# Vss.net
KiCad netlist of a schematic drawn in Altium Designer
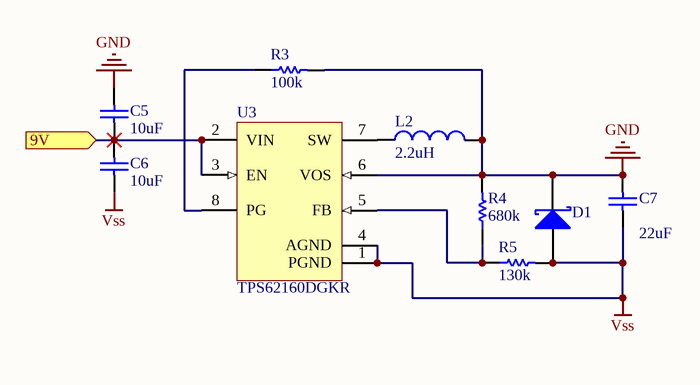
[diagram p0: Vss.SchDoc]

(export (version "E")
  (design (tool "Eeschema 10.0.6"))
  (components
    (comp (ref "C5")
      (value "10uF")
      (footprint "C1206")
      (description "Capacitor")
      (fields (field (name "Comment") "Cap") (field (name "PUBLISHER") "Altium Limited"))
      (libsource (lib "Miscellaneous Devices") (part "Cap"))
    )
    (comp (ref "C6")
      (value "10uF")
      (footprint "C1206")
      (description "Capacitor")
      (fields (field (name "Comment") "Cap") (field (name "PUBLISHER") "Altium Limited"))
      (libsource (lib "Miscellaneous Devices") (part "Cap"))
    )
    (comp (ref "C7")
      (value "22uF")
      (footprint "C1206")
      (description "Capacitor")
      (fields (field (name "Comment") "Cap") (field (name "PUBLISHER") "Altium Limited"))
      (libsource (lib "Miscellaneous Devices") (part "Cap"))
    )
    (comp (ref "D1")
      (value "D Schottky")
      (footprint "425")
      (description "Schottky Diode")
      (fields (field (name "PUBLISHER") "Altium Limited"))
      (libsource (lib "Miscellaneous Devices") (part "D Schottky"))
    )
    (comp (ref "L2")
      (value "2.2uH")
      (footprint "1608[0603]")
      (description "Inductor")
      (fields (field (name "PUBLISHER") "Altium Limited"))
      (libsource (lib "Miscellaneous Devices") (part "Inductor"))
    )
    (comp (ref "R3")
      (value "100k")
      (footprint "C1206")
      (description "Resistor")
      (fields (field (name "Comment") "Res1") (field (name "PUBLISHER") "Altium Limited"))
      (libsource (lib "Miscellaneous Devices") (part "Res1"))
    )
    (comp (ref "R4")
      (value "680k")
      (footprint "C1206")
      (description "Resistor")
      (fields (field (name "Comment") "Res1") (field (name "PUBLISHER") "Altium Limited"))
      (libsource (lib "Miscellaneous Devices") (part "Res1"))
    )
    (comp (ref "R5")
      (value "130k")
      (footprint "C1206")
      (description "Resistor")
      (fields (field (name "Comment") "Res1") (field (name "PUBLISHER") "Altium Limited"))
      (libsource (lib "Miscellaneous Devices") (part "Res1"))
    )
    (comp (ref "U3")
      (value "TPS62160DGKR")
      (footprint "DGK8_N")
      (fields (field (name "MANUFACTURER") "Texas Instruments"))
      (libsource (lib "TI Power Management Step-Down Regulator") (part "TPS62160DGKR"))
    )
  )
  (nets
    (net (code "1") (name "/9V") (class "Default")
      (node (ref "C5") (pin "1") (pinfunction "1_1") (pintype "passive"))
      (node (ref "C6") (pin "2") (pinfunction "2_2") (pintype "passive"))
      (node (ref "U3") (pin "2") (pinfunction "VIN_2") (pintype "power_in"))
      (node (ref "U3") (pin "3") (pinfunction "EN_3") (pintype "input"))
    )
    (net (code "2") (name "GND") (class "Default")
      (node (ref "C5") (pin "2") (pinfunction "2_2") (pintype "passive"))
      (node (ref "C7") (pin "2") (pinfunction "2_2") (pintype "passive"))
      (node (ref "D1") (pin "2") (pinfunction "K_2") (pintype "passive"))
      (node (ref "L2") (pin "2") (pinfunction "2_2") (pintype "passive"))
      (node (ref "R3") (pin "2") (pinfunction "2_2") (pintype "passive"))
      (node (ref "R4") (pin "2") (pinfunction "2_2") (pintype "passive"))
      (node (ref "U3") (pin "6") (pinfunction "VOS_6") (pintype "input"))
    )
    (net (code "3") (name "Net-(U3-FB)") (class "Default")
      (node (ref "R4") (pin "1") (pinfunction "1_1") (pintype "passive"))
      (node (ref "R5") (pin "1") (pinfunction "1_1") (pintype "passive"))
      (node (ref "U3") (pin "5") (pinfunction "FB_5") (pintype "input"))
    )
    (net (code "4") (name "Net-(U3-PG)") (class "Default")
      (node (ref "R3") (pin "1") (pinfunction "1_1") (pintype "passive"))
      (node (ref "U3") (pin "8") (pinfunction "PG_8") (pintype "tri_state"))
    )
    (net (code "5") (name "Net-(U3-SW)") (class "Default")
      (node (ref "L2") (pin "1") (pinfunction "1_1") (pintype "passive"))
      (node (ref "U3") (pin "7") (pinfunction "SW_7") (pintype "power_in"))
    )
    (net (code "6") (name "Vss") (class "Default")
      (node (ref "C6") (pin "1") (pinfunction "1_1") (pintype "passive"))
      (node (ref "C7") (pin "1") (pinfunction "1_1") (pintype "passive"))
      (node (ref "D1") (pin "1") (pinfunction "A_1") (pintype "passive"))
      (node (ref "R5") (pin "2") (pinfunction "2_2") (pintype "passive"))
      (node (ref "U3") (pin "1") (pinfunction "PGND_1") (pintype "power_in"))
      (node (ref "U3") (pin "4") (pinfunction "AGND_4") (pintype "power_in"))
    )
  )
)
